# mbedshield050.net
KiCad netlist of a schematic drawn in EAGLE
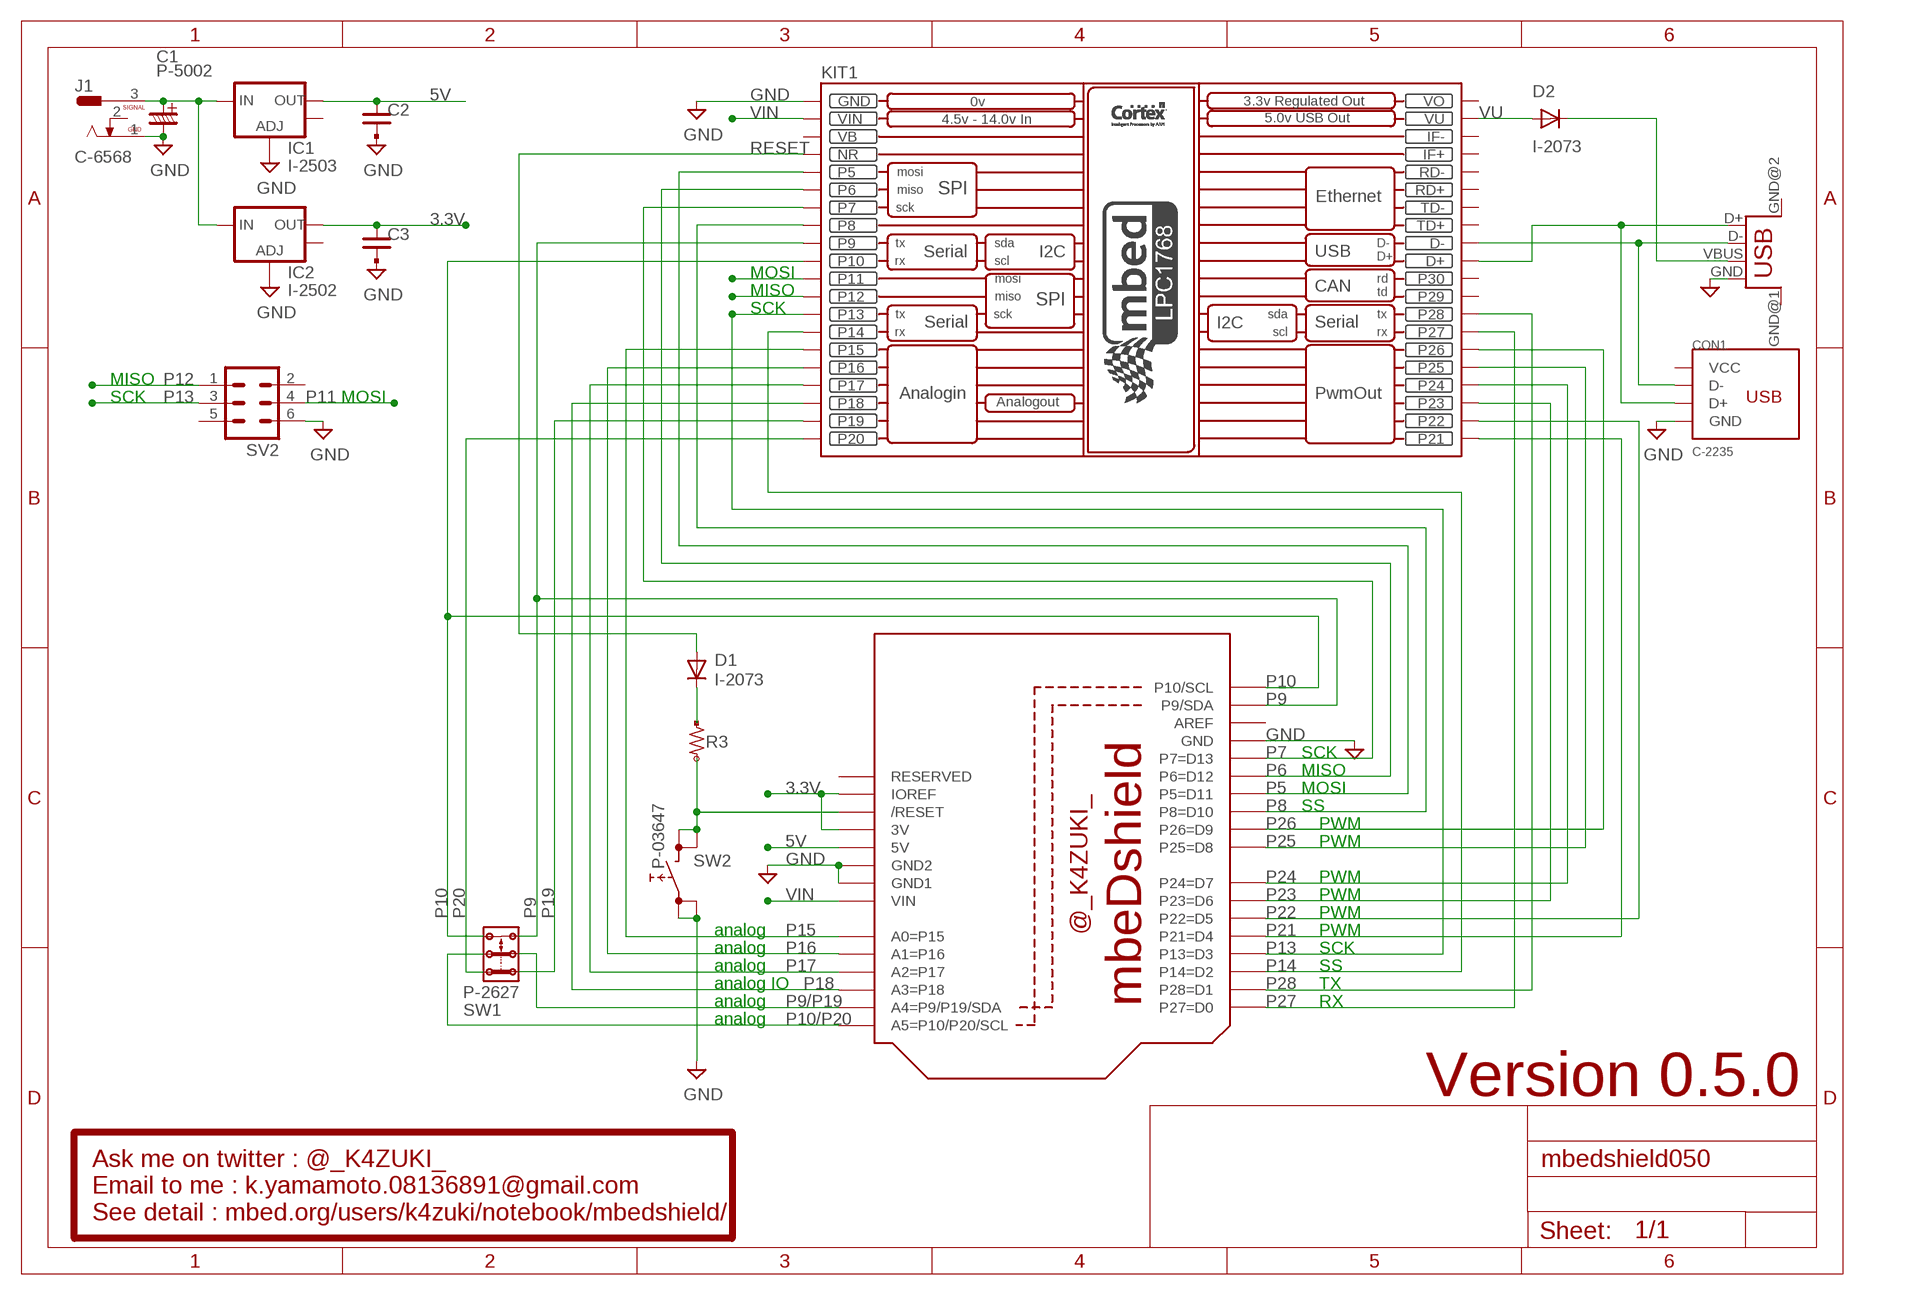
[diagram p0: schematic, sheet 1]

(export (version "E")
  (design (tool "Eeschema 10.0.6"))
  (components
    (comp (ref "C1")
      (value "P-5002")
      (footprint "eagle-import:C_2.5PHI6")
      (libsource (lib "eagle-import") (part "C_DENKAI_2.5P6"))
    )
    (comp (ref "C2")
      (value "C_PAD_PAD_1608")
      (footprint "eagle-import:CR_1608")
      (libsource (lib "eagle-import") (part "C_PAD_PAD_1608"))
    )
    (comp (ref "C3")
      (value "C_PAD_PAD_1608")
      (footprint "eagle-import:CR_1608")
      (libsource (lib "eagle-import") (part "C_PAD_PAD_1608"))
    )
    (comp (ref "CON1")
      (value "C-2235")
      (footprint "eagle-import:CON_USB_MINIB_AKI")
      (libsource (lib "eagle-import") (part "CON_USB"))
    )
    (comp (ref "D1")
      (value "I-2073")
      (footprint "eagle-import:SOD80C")
      (libsource (lib "eagle-import") (part "PMLL4150"))
    )
    (comp (ref "D2")
      (value "I-2073")
      (footprint "eagle-import:SOD80C")
      (libsource (lib "eagle-import") (part "PMLL4150"))
    )
    (comp (ref "IC1")
      (value "I-2503")
      (footprint "eagle-import:SOT223")
      (libsource (lib "eagle-import") (part "V_REG_LM1117SOT223"))
    )
    (comp (ref "IC2")
      (value "I-2502")
      (footprint "eagle-import:SOT223")
      (libsource (lib "eagle-import") (part "V_REG_LM1117SOT223"))
    )
    (comp (ref "J1")
      (value "C-6568")
      (footprint "eagle-import:CON_DCJACK")
      (libsource (lib "eagle-import") (part "CON_DCJACK1"))
    )
    (comp (ref "KIT1")
      (value "MBED_NXP_LPC1768")
      (footprint "eagle-import:MBED-KIT")
      (libsource (lib "eagle-import") (part "MBED_NXP_LPC1768"))
    )
    (comp (ref "R3")
      (value "R_US_PAD_VIA_2125")
      (footprint "eagle-import:R_2125_PADVIA")
      (libsource (lib "eagle-import") (part "R_US_PAD_VIA_2125"))
    )
    (comp (ref "SV2")
      (value "MA03-2")
      (footprint "eagle-import:MA03-2")
      (libsource (lib "eagle-import") (part "MA03-2"))
    )
    (comp (ref "SW1")
      (value "P-2627")
      (footprint "eagle-import:SW_SLIDE_2X2_1")
      (libsource (lib "eagle-import") (part "SW_SLIDESW_2_"))
    )
    (comp (ref "SW2")
      (value "P-03647")
      (footprint "eagle-import:SW_TACTSW_B3F-10XX")
      (libsource (lib "eagle-import") (part "SW_TACTSW_S2"))
    )
    (comp (ref "U$1")
      (value "BOARD_MBEDSHIELD2")
      (footprint "eagle-import:BOARD_MBEDSHIELD2")
      (libsource (lib "eagle-import") (part "BOARD_MBEDSHIELD2"))
    )
    (comp (ref "USB")
      (value "C-160")
      (footprint "eagle-import:USB-FEMALE-A-PTH")
      (libsource (lib "eagle-import") (part "USB"))
    )
  )
  (nets
    (net (code "1") (name "/3.3V") (class "Default")
      (node (ref "C3") (pin "P$1") (pinfunction "1_P$1") (pintype "passive"))
      (node (ref "IC2") (pin "2") (pinfunction "OUT_2") (pintype "output"))
      (node (ref "U$1") (pin "3V") (pinfunction "3V_3V") (pintype "power_in"))
      (node (ref "U$1") (pin "IOREF") (pinfunction "IOREF_IOREF") (pintype "output"))
    )
    (net (code "2") (name "/5V") (class "Default")
      (node (ref "C2") (pin "P$1") (pinfunction "1_P$1") (pintype "passive"))
      (node (ref "IC1") (pin "2") (pinfunction "OUT_2") (pintype "output"))
      (node (ref "U$1") (pin "5V") (pinfunction "5V_5V") (pintype "power_in"))
    )
    (net (code "3") (name "/P5") (class "Default")
      (node (ref "KIT1") (pin "P$5") (pinfunction "P5_P$5") (pintype "bidirectional"))
      (node (ref "U$1") (pin "D11") (pinfunction "P5=D11_D11") (pintype "bidirectional"))
    )
    (net (code "4") (name "/P6") (class "Default")
      (node (ref "KIT1") (pin "P$6") (pinfunction "P6_P$6") (pintype "bidirectional"))
      (node (ref "U$1") (pin "D12") (pinfunction "P6=D12_D12") (pintype "bidirectional"))
    )
    (net (code "5") (name "/P7") (class "Default")
      (node (ref "KIT1") (pin "P$7") (pinfunction "P7_P$7") (pintype "bidirectional"))
      (node (ref "U$1") (pin "D13") (pinfunction "P7=D13_D13") (pintype "bidirectional"))
    )
    (net (code "6") (name "/P8") (class "Default")
      (node (ref "KIT1") (pin "P$8") (pinfunction "P8_P$8") (pintype "bidirectional"))
      (node (ref "U$1") (pin "D10") (pinfunction "P8=D10_D10") (pintype "bidirectional"))
    )
    (net (code "7") (name "/P9") (class "Default")
      (node (ref "KIT1") (pin "P$9") (pinfunction "P9_P$9") (pintype "bidirectional"))
      (node (ref "SW1") (pin "2.1") (pinfunction "2.1_2.1") (pintype "passive"))
      (node (ref "U$1") (pin "SDA") (pinfunction "P9/SDA_SDA") (pintype "bidirectional"))
    )
    (net (code "8") (name "/P9{slash}P19") (class "Default")
      (node (ref "SW1") (pin "COM.1") (pinfunction "COM.1_COM.1") (pintype "passive"))
      (node (ref "U$1") (pin "A4") (pinfunction "A4=P9/P19/SDA_A4") (pintype "bidirectional"))
    )
    (net (code "9") (name "/P10") (class "Default")
      (node (ref "KIT1") (pin "P$10") (pinfunction "P10_P$10") (pintype "bidirectional"))
      (node (ref "SW1") (pin "2.2") (pinfunction "2.2_2.2") (pintype "passive"))
      (node (ref "U$1") (pin "SCL") (pinfunction "P10/SCL_SCL") (pintype "bidirectional"))
    )
    (net (code "10") (name "/P10{slash}P20") (class "Default")
      (node (ref "SW1") (pin "COM.2") (pinfunction "COM.2_COM.2") (pintype "passive"))
      (node (ref "U$1") (pin "A5") (pinfunction "A5=P10/P20/SCL_A5") (pintype "bidirectional"))
    )
    (net (code "11") (name "/P11") (class "Default")
      (node (ref "KIT1") (pin "P$11") (pinfunction "P11_P$11") (pintype "bidirectional"))
      (node (ref "SV2") (pin "4") (pinfunction "4_4") (pintype "passive"))
    )
    (net (code "12") (name "/P12") (class "Default")
      (node (ref "KIT1") (pin "P$12") (pinfunction "P12_P$12") (pintype "bidirectional"))
      (node (ref "SV2") (pin "1") (pinfunction "1_1") (pintype "passive"))
    )
    (net (code "13") (name "/P13") (class "Default")
      (node (ref "KIT1") (pin "P$13") (pinfunction "P13_P$13") (pintype "bidirectional"))
      (node (ref "SV2") (pin "3") (pinfunction "3_3") (pintype "passive"))
      (node (ref "U$1") (pin "D3") (pinfunction "P13=D3_D3") (pintype "bidirectional"))
    )
    (net (code "14") (name "/P14") (class "Default")
      (node (ref "KIT1") (pin "P$14") (pinfunction "P14_P$14") (pintype "bidirectional"))
      (node (ref "U$1") (pin "D2") (pinfunction "P14=D2_D2") (pintype "bidirectional"))
    )
    (net (code "15") (name "/P15") (class "Default")
      (node (ref "KIT1") (pin "P$15") (pinfunction "P15_P$15") (pintype "bidirectional"))
      (node (ref "U$1") (pin "A0") (pinfunction "A0=P15_A0") (pintype "bidirectional"))
    )
    (net (code "16") (name "/P16") (class "Default")
      (node (ref "KIT1") (pin "P$16") (pinfunction "P16_P$16") (pintype "bidirectional"))
      (node (ref "U$1") (pin "A1") (pinfunction "A1=P16_A1") (pintype "bidirectional"))
    )
    (net (code "17") (name "/P17") (class "Default")
      (node (ref "KIT1") (pin "P$17") (pinfunction "P17_P$17") (pintype "bidirectional"))
      (node (ref "U$1") (pin "A2") (pinfunction "A2=P17_A2") (pintype "bidirectional"))
    )
    (net (code "18") (name "/P18") (class "Default")
      (node (ref "KIT1") (pin "P$18") (pinfunction "P18_P$18") (pintype "bidirectional"))
      (node (ref "U$1") (pin "A3") (pinfunction "A3=P18_A3") (pintype "bidirectional"))
    )
    (net (code "19") (name "/P19") (class "Default")
      (node (ref "KIT1") (pin "P$19") (pinfunction "P19_P$19") (pintype "bidirectional"))
      (node (ref "SW1") (pin "1.1") (pinfunction "1.1_1.1") (pintype "passive"))
    )
    (net (code "20") (name "/P20") (class "Default")
      (node (ref "KIT1") (pin "P$20") (pinfunction "P20_P$20") (pintype "bidirectional"))
      (node (ref "SW1") (pin "1.2") (pinfunction "1.2_1.2") (pintype "passive"))
    )
    (net (code "21") (name "/P21") (class "Default")
      (node (ref "KIT1") (pin "P$21") (pinfunction "P21_P$21") (pintype "bidirectional"))
      (node (ref "U$1") (pin "D4") (pinfunction "P21=D4_D4") (pintype "bidirectional"))
    )
    (net (code "22") (name "/P22") (class "Default")
      (node (ref "KIT1") (pin "P$22") (pinfunction "P22_P$22") (pintype "bidirectional"))
      (node (ref "U$1") (pin "D5") (pinfunction "P22=D5_D5") (pintype "bidirectional"))
    )
    (net (code "23") (name "/P23") (class "Default")
      (node (ref "KIT1") (pin "P$23") (pinfunction "P23_P$23") (pintype "bidirectional"))
      (node (ref "U$1") (pin "D6") (pinfunction "P23=D6_D6") (pintype "bidirectional"))
    )
    (net (code "24") (name "/P24") (class "Default")
      (node (ref "KIT1") (pin "P$24") (pinfunction "P24_P$24") (pintype "bidirectional"))
      (node (ref "U$1") (pin "D7") (pinfunction "P24=D7_D7") (pintype "bidirectional"))
    )
    (net (code "25") (name "/P25") (class "Default")
      (node (ref "KIT1") (pin "P$25") (pinfunction "P25_P$25") (pintype "bidirectional"))
      (node (ref "U$1") (pin "D8") (pinfunction "P25=D8_D8") (pintype "bidirectional"))
    )
    (net (code "26") (name "/P26") (class "Default")
      (node (ref "KIT1") (pin "P$26") (pinfunction "P26_P$26") (pintype "bidirectional"))
      (node (ref "U$1") (pin "D9") (pinfunction "P26=D9_D9") (pintype "bidirectional"))
    )
    (net (code "27") (name "/P27") (class "Default")
      (node (ref "KIT1") (pin "P$27") (pinfunction "P27_P$27") (pintype "bidirectional"))
      (node (ref "U$1") (pin "D0") (pinfunction "P27=D0_D0") (pintype "bidirectional"))
    )
    (net (code "28") (name "/P28") (class "Default")
      (node (ref "KIT1") (pin "P$28") (pinfunction "P28_P$28") (pintype "bidirectional"))
      (node (ref "U$1") (pin "D1") (pinfunction "P28=D1_D1") (pintype "bidirectional"))
    )
    (net (code "29") (name "/RESET") (class "Default")
      (node (ref "D1") (pin "A") (pinfunction "A_A") (pintype "passive"))
      (node (ref "KIT1") (pin "NR") (pinfunction "NR_NR") (pintype "power_in"))
    )
    (net (code "30") (name "/VB") (class "Default")
      (node (ref "KIT1") (pin "VB") (pinfunction "VB_VB") (pintype "power_in"))
    )
    (net (code "31") (name "/VIN") (class "Default")
      (node (ref "C1") (pin "+") (pinfunction "+_+") (pintype "passive"))
      (node (ref "IC1") (pin "3") (pinfunction "IN_3") (pintype "input"))
      (node (ref "IC2") (pin "3") (pinfunction "IN_3") (pintype "input"))
      (node (ref "J1") (pin "3") (pinfunction "1_3") (pintype "passive"))
      (node (ref "KIT1") (pin "VIN") (pinfunction "VIN_VIN") (pintype "power_in"))
      (node (ref "U$1") (pin "VIN") (pinfunction "VIN_VIN") (pintype "power_in"))
    )
    (net (code "32") (name "/VO") (class "Default")
      (node (ref "KIT1") (pin "VOUT") (pinfunction "VO_VOUT") (pintype "power_in"))
    )
    (net (code "33") (name "/VU") (class "Default")
      (node (ref "D2") (pin "A") (pinfunction "A_A") (pintype "passive"))
      (node (ref "KIT1") (pin "VU") (pinfunction "VU_VU") (pintype "power_in"))
    )
    (net (code "34") (name "GND") (class "Default")
      (node (ref "C1") (pin "-") (pinfunction "-_-") (pintype "passive"))
      (node (ref "C2") (pin "P$2") (pinfunction "2_P$2") (pintype "passive"))
      (node (ref "C3") (pin "P$2") (pinfunction "2_P$2") (pintype "passive"))
      (node (ref "CON1") (pin "GND") (pinfunction "GND_GND") (pintype "bidirectional"))
      (node (ref "IC1") (pin "1") (pinfunction "ADJ_1") (pintype "input"))
      (node (ref "IC2") (pin "1") (pinfunction "ADJ_1") (pintype "input"))
      (node (ref "J1") (pin "1") (pinfunction "3_1") (pintype "passive"))
      (node (ref "KIT1") (pin "GND") (pinfunction "GND_GND") (pintype "power_in"))
      (node (ref "SV2") (pin "6") (pinfunction "6_6") (pintype "passive"))
      (node (ref "SW2") (pin "1") (pinfunction "0_1") (pintype "passive"))
      (node (ref "SW2") (pin "2") (pinfunction "0_2") (pintype "passive"))
      (node (ref "U$1") (pin "GND") (pinfunction "GND_GND") (pintype "power_in"))
      (node (ref "U$1") (pin "GND1") (pinfunction "GND1_GND1") (pintype "power_in"))
      (node (ref "U$1") (pin "GND2") (pinfunction "GND2_GND2") (pintype "power_in"))
      (node (ref "USB") (pin "GND") (pinfunction "GND_GND") (pintype "bidirectional"))
    )
    (net (code "35") (name "Net-(CON1-PadD+)") (class "Default")
      (node (ref "CON1") (pin "D+") (pinfunction "D+_D+") (pintype "bidirectional"))
      (node (ref "KIT1") (pin "D+") (pinfunction "D+_D+") (pintype "bidirectional"))
      (node (ref "USB") (pin "D+") (pinfunction "D+_D+") (pintype "bidirectional"))
    )
    (net (code "36") (name "Net-(CON1-PadD-)") (class "Default")
      (node (ref "CON1") (pin "D-") (pinfunction "D-_D-") (pintype "bidirectional"))
      (node (ref "KIT1") (pin "D-") (pinfunction "D-_D-") (pintype "bidirectional"))
      (node (ref "USB") (pin "D-") (pinfunction "D-_D-") (pintype "bidirectional"))
    )
    (net (code "37") (name "Net-(D1-PadC)") (class "Default")
      (node (ref "D1") (pin "C") (pinfunction "C_C") (pintype "passive"))
      (node (ref "R3") (pin "PAD") (pinfunction "PAD_PAD") (pintype "passive"))
    )
    (net (code "38") (name "Net-(D2-PadC)") (class "Default")
      (node (ref "D2") (pin "C") (pinfunction "C_C") (pintype "passive"))
      (node (ref "USB") (pin "VBUS") (pinfunction "VBUS_VBUS") (pintype "bidirectional"))
    )
    (net (code "39") (name "Net-(U$1-{slash}RESET)") (class "Default")
      (node (ref "R3") (pin "VIA") (pinfunction "VIA_VIA") (pintype "passive"))
      (node (ref "SW2") (pin "3") (pinfunction "1_3") (pintype "passive"))
      (node (ref "SW2") (pin "4") (pinfunction "1_4") (pintype "passive"))
      (node (ref "U$1") (pin "RESET") (pinfunction "/RESET_RESET") (pintype "bidirectional"))
    )
    (net (code "40") (name "unconnected-(CON1-VCC-PadVBUS)") (class "Default")
      (node (ref "CON1") (pin "VBUS") (pinfunction "VCC_VBUS") (pintype "bidirectional"))
    )
    (net (code "41") (name "unconnected-(IC1-OUT-Pad4)") (class "Default")
      (node (ref "IC1") (pin "4") (pinfunction "OUT_4") (pintype "output"))
    )
    (net (code "42") (name "unconnected-(IC2-OUT-Pad4)") (class "Default")
      (node (ref "IC2") (pin "4") (pinfunction "OUT_4") (pintype "output"))
    )
    (net (code "43") (name "unconnected-(J1-Pad2)") (class "Default")
      (node (ref "J1") (pin "2") (pinfunction "2_2") (pintype "passive"))
    )
    (net (code "44") (name "unconnected-(KIT1-P29-PadP$29)") (class "Default")
      (node (ref "KIT1") (pin "P$29") (pinfunction "P29_P$29") (pintype "bidirectional"))
    )
    (net (code "45") (name "unconnected-(KIT1-P30-PadP$30)") (class "Default")
      (node (ref "KIT1") (pin "P$30") (pinfunction "P30_P$30") (pintype "bidirectional"))
    )
    (net (code "46") (name "unconnected-(KIT1-PadIF+)") (class "Default")
      (node (ref "KIT1") (pin "IF+") (pinfunction "IF+_IF+") (pintype "bidirectional"))
    )
    (net (code "47") (name "unconnected-(KIT1-PadIF-)") (class "Default")
      (node (ref "KIT1") (pin "IF-") (pinfunction "IF-_IF-") (pintype "bidirectional"))
    )
    (net (code "48") (name "unconnected-(KIT1-PadRD+)") (class "Default")
      (node (ref "KIT1") (pin "RD+") (pinfunction "RD+_RD+") (pintype "bidirectional"))
    )
    (net (code "49") (name "unconnected-(KIT1-PadRD-)") (class "Default")
      (node (ref "KIT1") (pin "RD-") (pinfunction "RD-_RD-") (pintype "bidirectional"))
    )
    (net (code "50") (name "unconnected-(KIT1-PadTD+)") (class "Default")
      (node (ref "KIT1") (pin "TD+") (pinfunction "TD+_TD+") (pintype "bidirectional"))
    )
    (net (code "51") (name "unconnected-(KIT1-PadTD-)") (class "Default")
      (node (ref "KIT1") (pin "TD-") (pinfunction "TD-_TD-") (pintype "bidirectional"))
    )
    (net (code "52") (name "unconnected-(SV2-Pad2)") (class "Default")
      (node (ref "SV2") (pin "2") (pinfunction "2_2") (pintype "passive"))
    )
    (net (code "53") (name "unconnected-(SV2-Pad5)") (class "Default")
      (node (ref "SV2") (pin "5") (pinfunction "5_5") (pintype "passive"))
    )
    (net (code "54") (name "unconnected-(U$1-PadAREF)") (class "Default")
      (node (ref "U$1") (pin "AREF") (pinfunction "AREF_AREF") (pintype "bidirectional"))
    )
    (net (code "55") (name "unconnected-(U$1-PadRESERVED)") (class "Default")
      (node (ref "U$1") (pin "RESERVED") (pinfunction "RESERVED_RESERVED") (pintype "no_connect"))
    )
    (net (code "56") (name "unconnected-(USB-GND-PadGND@1)") (class "Default")
      (node (ref "USB") (pin "GND@1") (pinfunction "GND_GND@1") (pintype "bidirectional"))
    )
    (net (code "57") (name "unconnected-(USB-GND-PadGND@2)") (class "Default")
      (node (ref "USB") (pin "GND@2") (pinfunction "GND_GND@2") (pintype "bidirectional"))
    )
  )
)
